# ProPrj_Loongson_Aquarii_v1_7.net
KiCad netlist of a schematic drawn in EasyEDA Pro
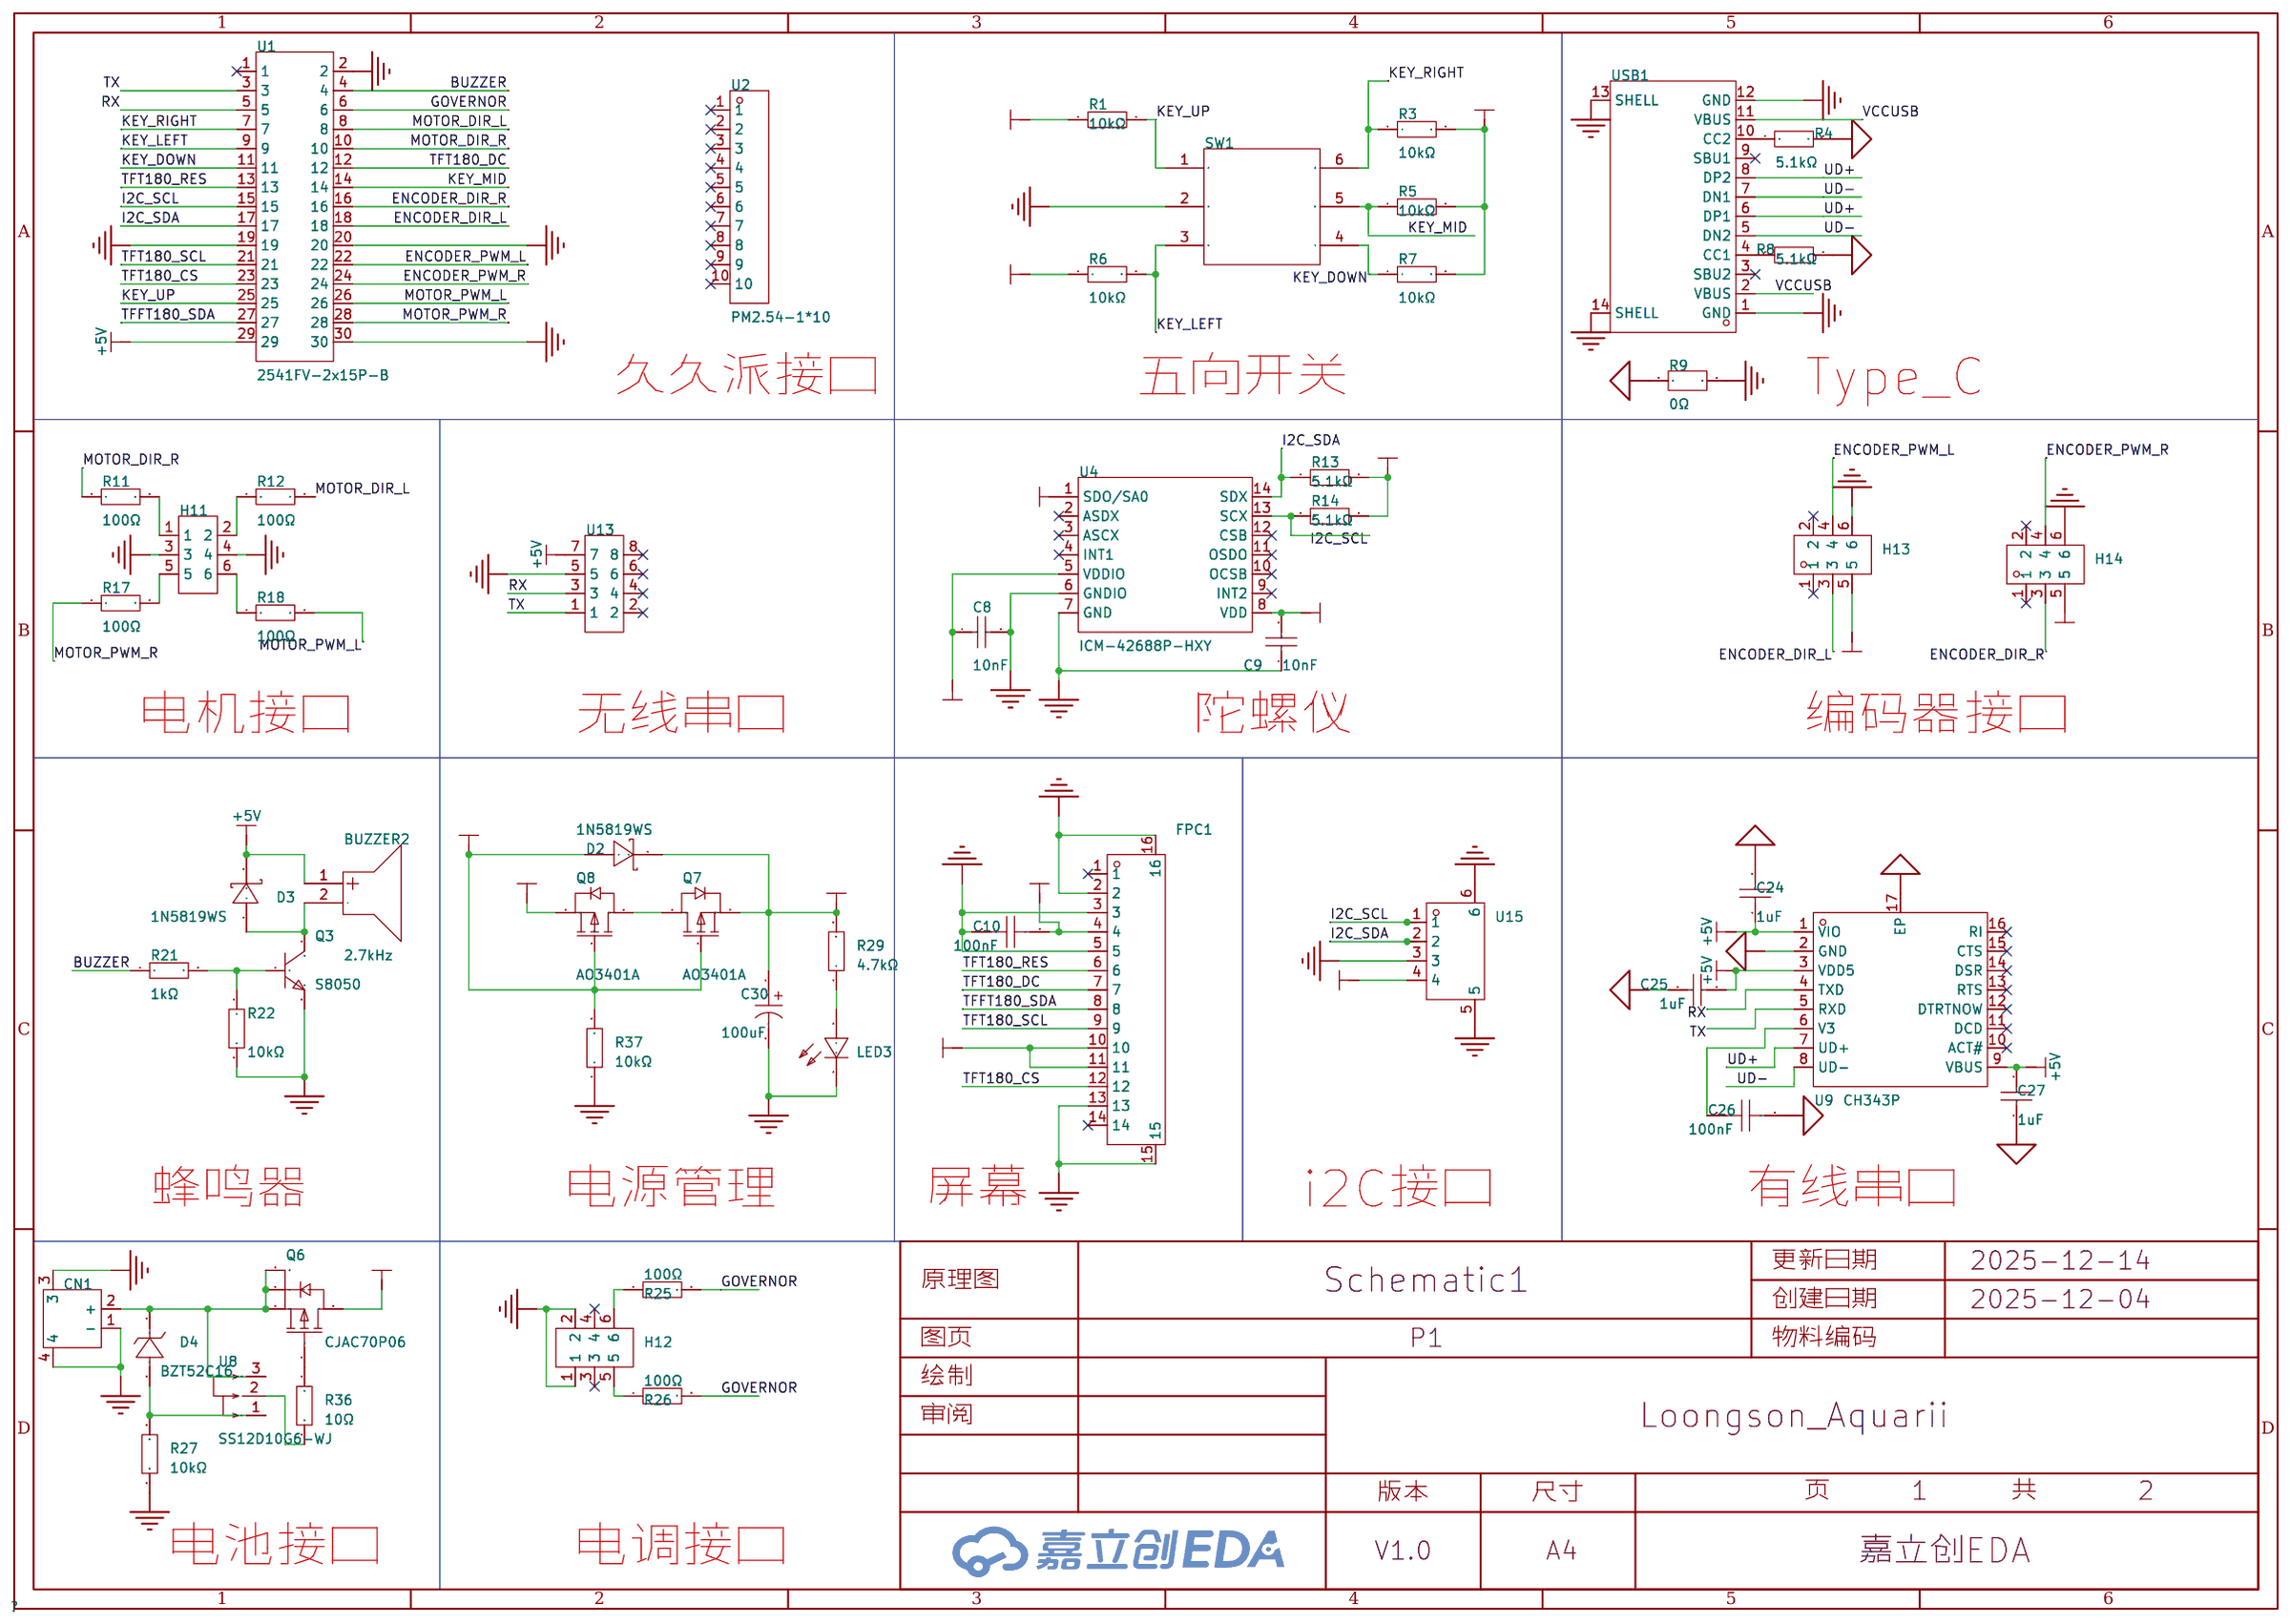
[diagram p0: P1]
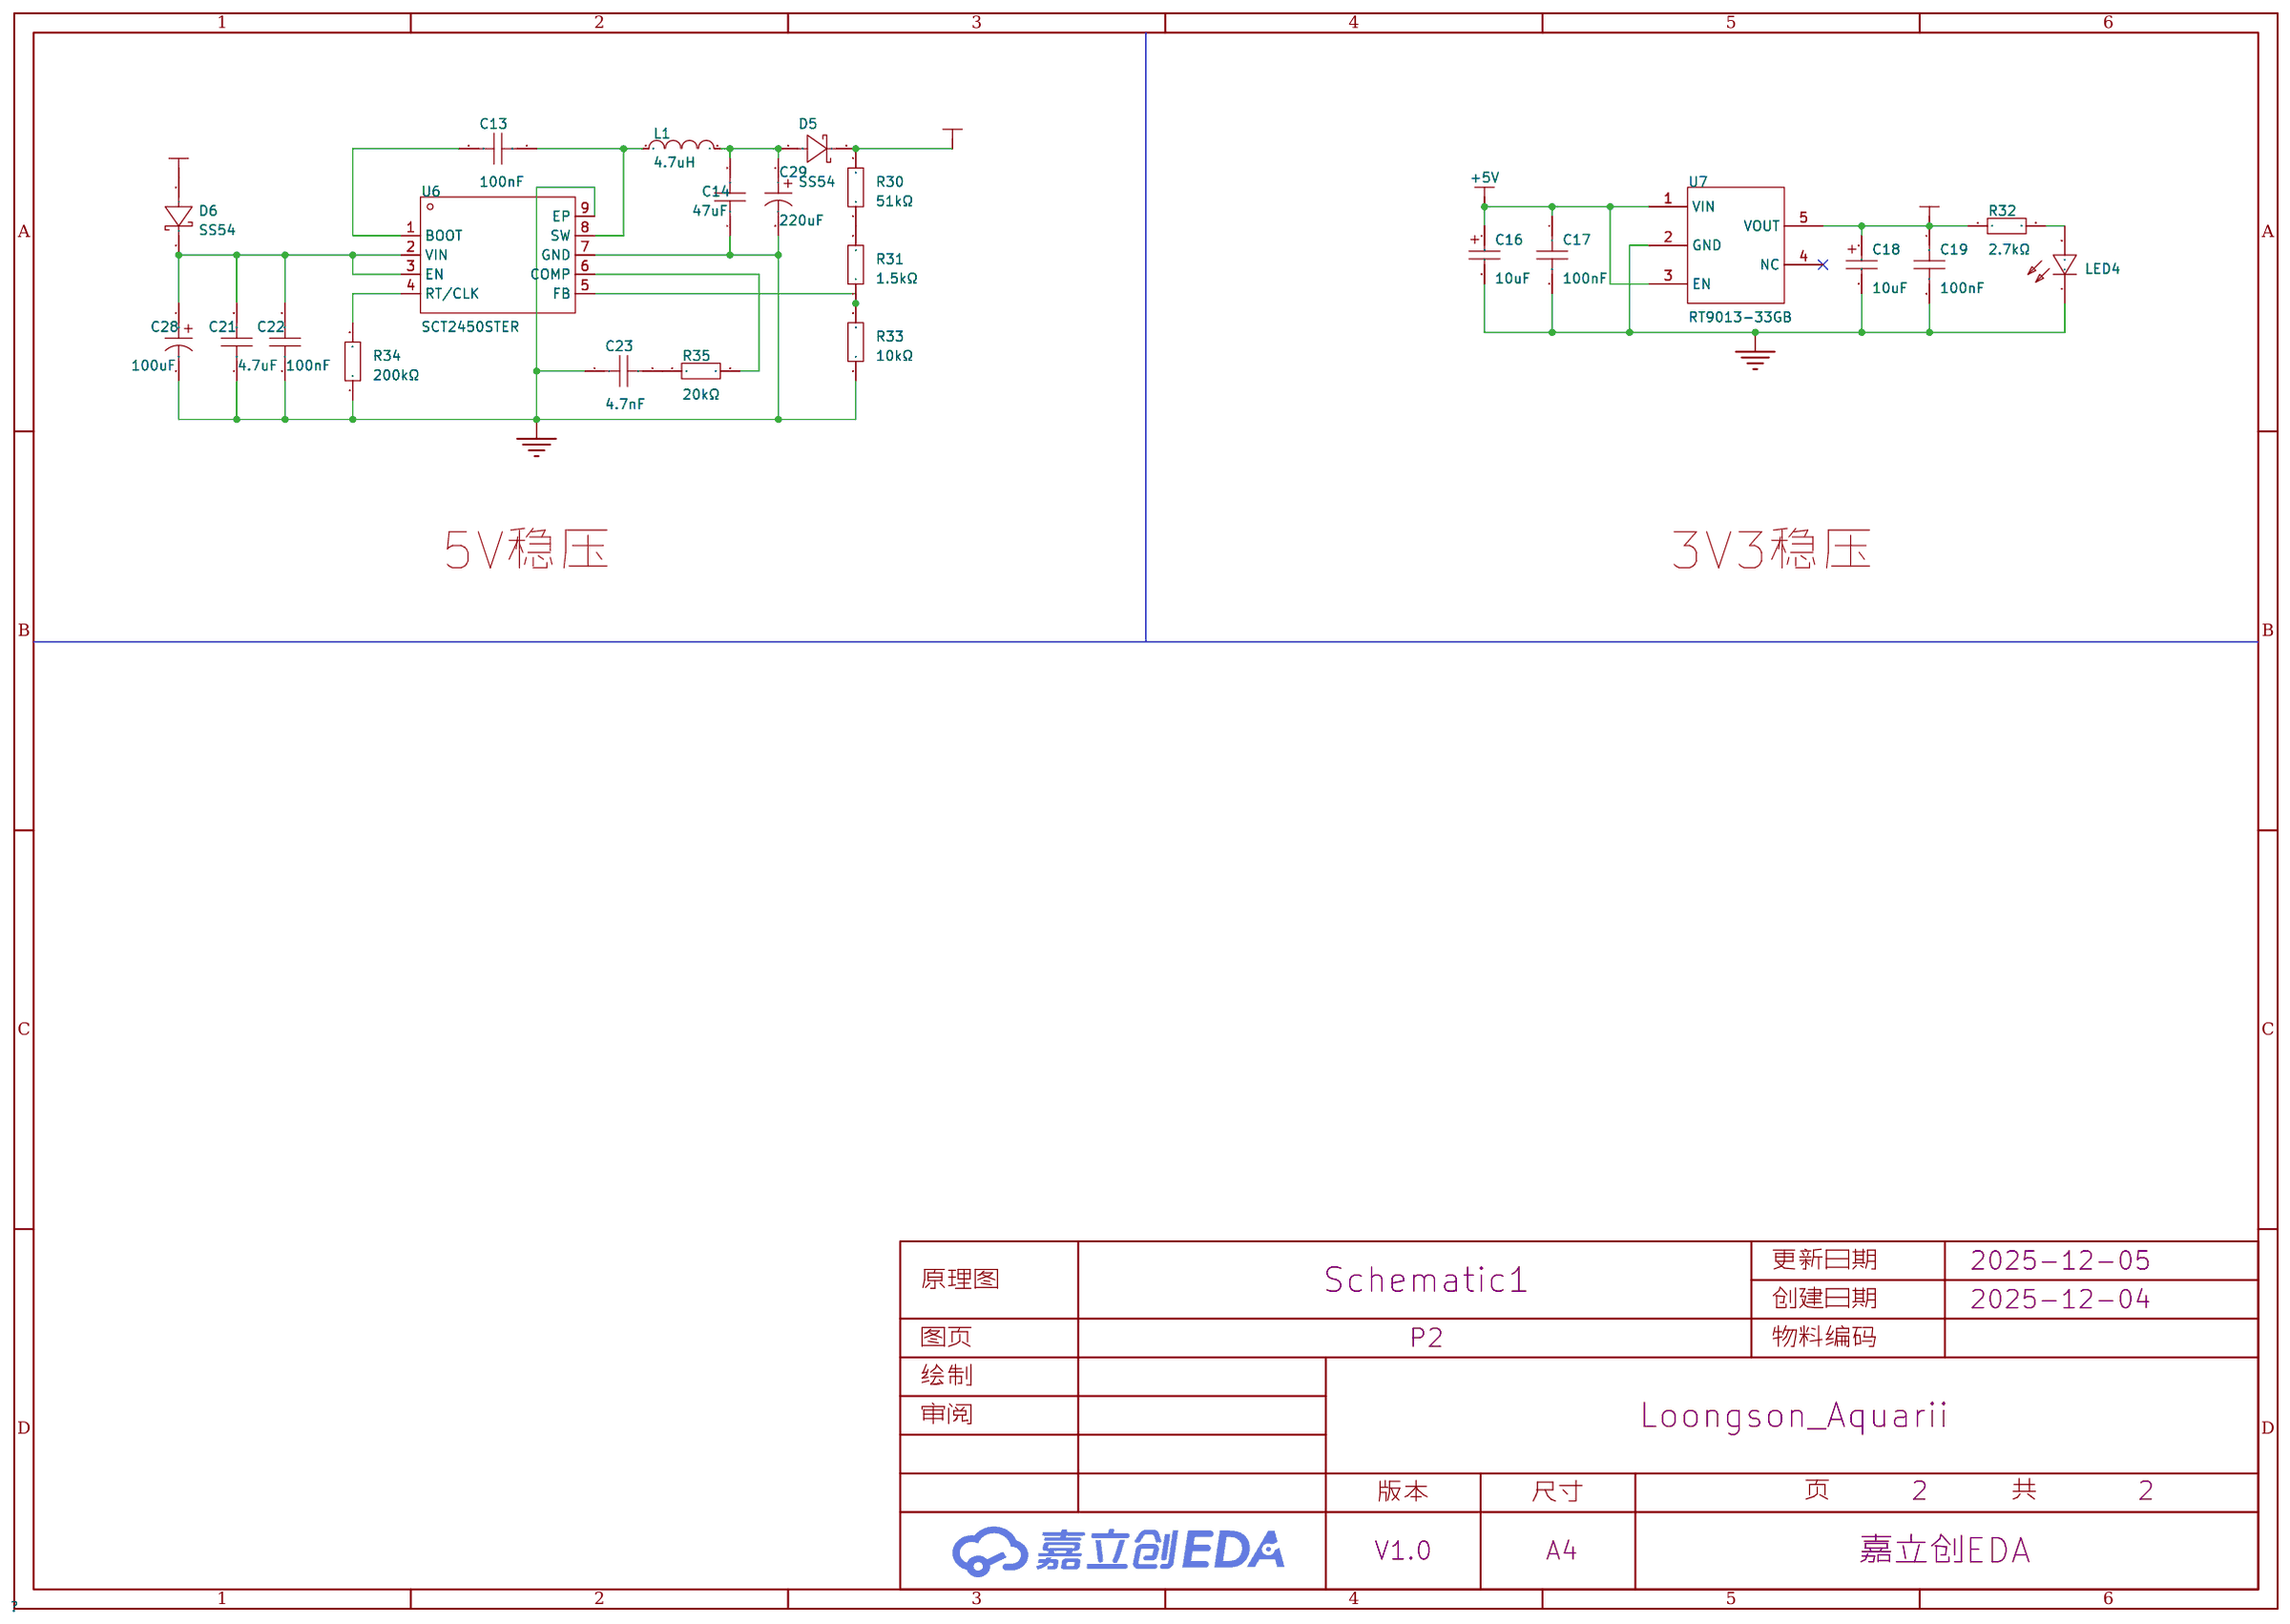
[diagram p1: P2]

(export (version "E")
  (design (tool "Eeschema 10.0.6"))
  (components
    (comp (ref "BUZZER2")
      (value "2.7kHz")
      (footprint "easyedapro:BUZ-SMD_GSC9032RB")
      (description "驱动方式:无源(外部驱动);构造类型:电磁式;额定电压:3.6V;频率:2.7kHz;声压(SPL):85dB;")
      (fields
        (field (name "Manufacturer Part") "GSC9032RB-16R2700")
        (field (name "Manufacturer") "INGHAi(赢海)")
      )
      (libsource (lib "easyedapro") (part "GSC9032RB-16R2700"))
    )
    (comp (ref "C8")
      (value "10nF")
      (footprint "easyedapro:C0603")
      (description "容值:10nF;精度:±10%;额定电压:50V;温度系数:X7R;")
      (fields
        (field (name "Manufacturer Part") "CC0603KRX7R9BB103")
        (field (name "Manufacturer") "YAGEO(国巨)")
      )
      (libsource (lib "easyedapro") (part "CC0603KRX7R9BB103"))
    )
    (comp (ref "C9")
      (value "10nF")
      (footprint "easyedapro:C0603")
      (description "容值:10nF;精度:±10%;额定电压:50V;温度系数:X7R;")
      (fields
        (field (name "Manufacturer Part") "CC0603KRX7R9BB103")
        (field (name "Manufacturer") "YAGEO(国巨)")
      )
      (libsource (lib "easyedapro") (part "CC0603KRX7R9BB103"))
    )
    (comp (ref "C10")
      (value "100nF")
      (footprint "easyedapro:C0603")
      (description "容值:100nF;精度:±10%;额定电压:50V;材质(温度系数):X7R;")
      (fields
        (field (name "Manufacturer Part") "CGA0603X7R104K500JT")
        (field (name "Manufacturer") "HRE(芯声)")
      )
      (libsource (lib "easyedapro") (part "CGA0603X7R104K500JT"))
    )
    (comp (ref "C24")
      (value "1uF")
      (footprint "easyedapro:C0805")
      (description "容值:1uF;精度:±10%;额定电压:50V;温度系数:X7R;")
      (fields
        (field (name "Manufacturer Part") "CL21B105KBFNNNE")
        (field (name "Manufacturer") "SAMSUNG(三星)")
      )
      (libsource (lib "easyedapro") (part "CL21B105KBFNNNE"))
    )
    (comp (ref "C25")
      (value "1uF")
      (footprint "easyedapro:C0805")
      (description "容值:1uF;精度:±10%;额定电压:50V;温度系数:X7R;")
      (fields
        (field (name "Manufacturer Part") "CL21B105KBFNNNE")
        (field (name "Manufacturer") "SAMSUNG(三星)")
      )
      (libsource (lib "easyedapro") (part "CL21B105KBFNNNE"))
    )
    (comp (ref "C26")
      (value "100nF")
      (footprint "easyedapro:C0603")
      (description "容值:100nF;精度:±10%;额定电压:50V;材质(温度系数):X7R;")
      (fields
        (field (name "Manufacturer Part") "CGA0603X7R104K500JT")
        (field (name "Manufacturer") "HRE(芯声)")
      )
      (libsource (lib "easyedapro") (part "CGA0603X7R104K500JT"))
    )
    (comp (ref "C27")
      (value "1uF")
      (footprint "easyedapro:C0805")
      (description "容值:1uF;精度:±10%;额定电压:50V;温度系数:X7R;")
      (fields
        (field (name "Manufacturer Part") "CL21B105KBFNNNE")
        (field (name "Manufacturer") "SAMSUNG(三星)")
      )
      (libsource (lib "easyedapro") (part "CL21B105KBFNNNE"))
    )
    (comp (ref "C30")
      (value "100uF")
      (footprint "easyedapro:CAP-SMD_BD6.3-L6.6-W6.6-FD-1")
      (description "容值:100uF;精度:±20%;额定电压:25V;纹波电流:72mA@120Hz;")
      (fields (field (name "Manufacturer Part") "JVJ25V100M6x5") (field (name "Manufacturer") "JIERR(捷而瑞)"))
      (libsource (lib "easyedapro") (part "JVJ25V100M6X5"))
    )
    (comp (ref "CN1")
      (value "XT30PW-M30.G.Y")
      (footprint "easyedapro:CONN-TH_XT30PW-M")
      (description "类别:-;类型1:-;")
      (fields (field (name "Manufacturer") "AMASS(艾迈斯)"))
      (libsource (lib "easyedapro") (part "XT30PW-M"))
    )
    (comp (ref "D2")
      (value "1N5819WS")
      (footprint "easyedapro:SOD-323_L1.8-W1.3-LS2.5-RD")
      (description "正向压降(Vf):600mV@1A;直流反向耐压(Vr):40V;整流电流:1A;")
      (fields (field (name "Manufacturer") "Hottech(合科泰)"))
      (libsource (lib "easyedapro") (part "1N5819WS"))
    )
    (comp (ref "D3")
      (value "1N5819WS")
      (footprint "easyedapro:SOD-323_L1.8-W1.3-LS2.5-RD")
      (description "正向压降(Vf):600mV@1A;直流反向耐压(Vr):40V;整流电流:1A;")
      (fields (field (name "Manufacturer") "Hottech(合科泰)"))
      (libsource (lib "easyedapro") (part "1N5819WS"))
    )
    (comp (ref "D4")
      (value "BZT52C16")
      (footprint "easyedapro:SOD-123_L2.7-W1.6-LS3.7-RD")
      (description "二极管配置:独立式;稳压值(标称值):16V;稳压值(范围):15.2V~16.8V;耗散功率(Pd):500mW;")
      (fields (field (name "Manufacturer") "宏嘉诚"))
      (libsource (lib "easyedapro") (part "BZT52C16_C19077413"))
    )
    (comp (ref "FPC1")
      (value "HC-FPC-05-09-14RLTAG")
      (footprint "easyedapro:FPC-SMD_14P-P0.50_HC-FPC-05-09-14RLTAG")
      (description "锁定特性:翻盖式;触点类型:双侧触点/上下接;触点数量:14P;间距:0.5mm;安装方式:卧贴;工作温度:-55°C~+85°C;")
      (fields (field (name "Manufacturer") "HCTL(华灿天禄)"))
      (libsource (lib "easyedapro") (part "HC-FPC-05-09-14RLTAG"))
    )
    (comp (ref "H11")
      (value "HX PZ2.54-2x3P TP")
      (footprint "easyedapro:HDR-SMD_6P-P2.54-V-M-R2-C3-LS7.2_M20-8760342")
      (fields (field (name "Manufacturer") "hanxia(韩下)"))
      (libsource (lib "easyedapro") (part "HX PZ2.54-2X3P TP"))
    )
    (comp (ref "H12")
      (value "HX PZ2.54-2x3P TP")
      (footprint "easyedapro:HDR-SMD_6P-P2.54-V-M-R2-C3-LS7.2_M20-8760342")
      (fields (field (name "Manufacturer") "hanxia(韩下)"))
      (libsource (lib "easyedapro") (part "HX PZ2.54-2X3P TP"))
    )
    (comp (ref "H13")
      (value "PZ254V-12-6P")
      (footprint "easyedapro:HDR-TH_6P-P2.54-V-M-R2-C3-S2.54")
      (fields (field (name "Manufacturer") "XFCN(兴飞)"))
      (libsource (lib "easyedapro") (part "PZ254V-12-6P"))
    )
    (comp (ref "H14")
      (value "PZ254V-12-6P")
      (footprint "easyedapro:HDR-TH_6P-P2.54-V-M-R2-C3-S2.54")
      (fields (field (name "Manufacturer") "XFCN(兴飞)"))
      (libsource (lib "easyedapro") (part "PZ254V-12-6P"))
    )
    (comp (ref "LED3")
      (value "NCD0603R1")
      (footprint "easyedapro:LED0603-RD_RED")
      (fields (field (name "Manufacturer") "国星光电"))
      (libsource (lib "easyedapro") (part "FC-DA1608HRK-620D"))
    )
    (comp (ref "Q3")
      (value "S8050")
      (footprint "easyedapro:SOT-23-3_L2.9-W1.6-P1.90-LS2.8-BR")
      (description "晶体管类型:NPN;集电极电流(Ic):500mA;集射极击穿电压(Vceo):25V;功率(Pd):300mW;")
      (fields (field (name "Manufacturer") "Hottech(合科泰)"))
      (libsource (lib "easyedapro") (part "S8050_C181158"))
    )
    (comp (ref "Q6")
      (value "CJAC70P06")
      (footprint "easyedapro:TDSON-8_L5.9-W5.2-P1.27-BL")
      (fields (field (name "Manufacturer") "CJ(江苏长电/长晶)"))
      (libsource (lib "easyedapro") (part "CJAC70P06"))
    )
    (comp (ref "Q7")
      (value "AO3401A")
      (footprint "easyedapro:SOT-23_L2.9-W1.3-P1.90-LS2.4-BR")
      (fields (field (name "Manufacturer") "UMW(友台半导体)"))
      (libsource (lib "easyedapro") (part "AO3401A_C347476"))
    )
    (comp (ref "Q8")
      (value "AO3401A")
      (footprint "easyedapro:SOT-23_L2.9-W1.3-P1.90-LS2.4-BR")
      (fields (field (name "Manufacturer") "UMW(友台半导体)"))
      (libsource (lib "easyedapro") (part "AO3401A_C347476"))
    )
    (comp (ref "R1")
      (value "10kΩ")
      (footprint "easyedapro:R0603")
      (description "电阻类型:厚膜电阻;阻值:10kΩ;精度:±1%;功率:100mW;最大工作电压:75V;温度系数:±100ppm/°C;")
      (fields
        (field (name "Manufacturer Part") "0603WAF1002T5E")
        (field (name "Manufacturer") "UNI-ROYAL(厚声)")
      )
      (libsource (lib "easyedapro") (part "0603WAF1002T5E"))
    )
    (comp (ref "R3")
      (value "10kΩ")
      (footprint "easyedapro:R0603")
      (description "电阻类型:厚膜电阻;阻值:10kΩ;精度:±1%;功率:100mW;最大工作电压:75V;温度系数:±100ppm/°C;")
      (fields
        (field (name "Manufacturer Part") "0603WAF1002T5E")
        (field (name "Manufacturer") "UNI-ROYAL(厚声)")
      )
      (libsource (lib "easyedapro") (part "0603WAF1002T5E"))
    )
    (comp (ref "R4")
      (value "5.1kΩ")
      (footprint "easyedapro:R0603")
      (description "电阻类型:厚膜电阻;阻值:5.1kΩ;精度:±1%;功率:100mW;最大工作电压:75V;温度系数:±100ppm/°C;")
      (fields
        (field (name "Manufacturer Part") "0603WAF5101T5E")
        (field (name "Manufacturer") "UNI-ROYAL(厚声)")
      )
      (libsource (lib "easyedapro") (part "0603WAF5101T5E"))
    )
    (comp (ref "R5")
      (value "10kΩ")
      (footprint "easyedapro:R0603")
      (description "电阻类型:厚膜电阻;阻值:10kΩ;精度:±1%;功率:100mW;最大工作电压:75V;温度系数:±100ppm/°C;")
      (fields
        (field (name "Manufacturer Part") "0603WAF1002T5E")
        (field (name "Manufacturer") "UNI-ROYAL(厚声)")
      )
      (libsource (lib "easyedapro") (part "0603WAF1002T5E"))
    )
    (comp (ref "R6")
      (value "10kΩ")
      (footprint "easyedapro:R0603")
      (description "电阻类型:厚膜电阻;阻值:10kΩ;精度:±1%;功率:100mW;最大工作电压:75V;温度系数:±100ppm/°C;")
      (fields
        (field (name "Manufacturer Part") "0603WAF1002T5E")
        (field (name "Manufacturer") "UNI-ROYAL(厚声)")
      )
      (libsource (lib "easyedapro") (part "0603WAF1002T5E"))
    )
    (comp (ref "R7")
      (value "10kΩ")
      (footprint "easyedapro:R0603")
      (description "电阻类型:厚膜电阻;阻值:10kΩ;精度:±1%;功率:100mW;最大工作电压:75V;温度系数:±100ppm/°C;")
      (fields
        (field (name "Manufacturer Part") "0603WAF1002T5E")
        (field (name "Manufacturer") "UNI-ROYAL(厚声)")
      )
      (libsource (lib "easyedapro") (part "0603WAF1002T5E"))
    )
    (comp (ref "R8")
      (value "5.1kΩ")
      (footprint "easyedapro:R0603")
      (description "电阻类型:厚膜电阻;阻值:5.1kΩ;精度:±1%;功率:100mW;最大工作电压:75V;温度系数:±100ppm/°C;")
      (fields
        (field (name "Manufacturer Part") "0603WAF5101T5E")
        (field (name "Manufacturer") "UNI-ROYAL(厚声)")
      )
      (libsource (lib "easyedapro") (part "0603WAF5101T5E"))
    )
    (comp (ref "R9")
      (value "0Ω")
      (footprint "easyedapro:R1206")
      (description "电阻类型:厚膜电阻;阻值:0Ω;精度:±5%;功率:250mW;最大工作电压:200V;")
      (fields (field (name "Manufacturer Part") "FRC1206P000 TS") (field (name "Manufacturer") "FOJAN(富捷)"))
      (libsource (lib "easyedapro") (part "FRC1206P000 TS"))
    )
    (comp (ref "R11")
      (value "100Ω")
      (footprint "easyedapro:R0603")
      (description "电阻类型:厚膜电阻;阻值:100Ω;精度:±1%;功率:100mW;最大工作电压:75V;温度系数:±200ppm/°C;")
      (fields
        (field (name "Manufacturer Part") "0603WAF1000T5E")
        (field (name "Manufacturer") "UNI-ROYAL(厚声)")
      )
      (libsource (lib "easyedapro") (part "0603WAF1000T5E"))
    )
    (comp (ref "R12")
      (value "100Ω")
      (footprint "easyedapro:R0603")
      (description "电阻类型:厚膜电阻;阻值:100Ω;精度:±1%;功率:100mW;最大工作电压:75V;温度系数:±200ppm/°C;")
      (fields
        (field (name "Manufacturer Part") "0603WAF1000T5E")
        (field (name "Manufacturer") "UNI-ROYAL(厚声)")
      )
      (libsource (lib "easyedapro") (part "0603WAF1000T5E"))
    )
    (comp (ref "R13")
      (value "5.1kΩ")
      (footprint "easyedapro:R0603")
      (description "电阻类型:厚膜电阻;阻值:5.1kΩ;精度:±1%;功率:100mW;最大工作电压:75V;温度系数:±100ppm/°C;")
      (fields
        (field (name "Manufacturer Part") "0603WAF5101T5E")
        (field (name "Manufacturer") "UNI-ROYAL(厚声)")
      )
      (libsource (lib "easyedapro") (part "0603WAF5101T5E"))
    )
    (comp (ref "R14")
      (value "5.1kΩ")
      (footprint "easyedapro:R0603")
      (description "电阻类型:厚膜电阻;阻值:5.1kΩ;精度:±1%;功率:100mW;最大工作电压:75V;温度系数:±100ppm/°C;")
      (fields
        (field (name "Manufacturer Part") "0603WAF5101T5E")
        (field (name "Manufacturer") "UNI-ROYAL(厚声)")
      )
      (libsource (lib "easyedapro") (part "0603WAF5101T5E"))
    )
    (comp (ref "R17")
      (value "100Ω")
      (footprint "easyedapro:R0603")
      (description "电阻类型:厚膜电阻;阻值:100Ω;精度:±1%;功率:100mW;最大工作电压:75V;温度系数:±200ppm/°C;")
      (fields
        (field (name "Manufacturer Part") "0603WAF1000T5E")
        (field (name "Manufacturer") "UNI-ROYAL(厚声)")
      )
      (libsource (lib "easyedapro") (part "0603WAF1000T5E"))
    )
    (comp (ref "R18")
      (value "100Ω")
      (footprint "easyedapro:R0603")
      (description "电阻类型:厚膜电阻;阻值:100Ω;精度:±1%;功率:100mW;最大工作电压:75V;温度系数:±200ppm/°C;")
      (fields
        (field (name "Manufacturer Part") "0603WAF1000T5E")
        (field (name "Manufacturer") "UNI-ROYAL(厚声)")
      )
      (libsource (lib "easyedapro") (part "0603WAF1000T5E"))
    )
    (comp (ref "R21")
      (value "1kΩ")
      (footprint "easyedapro:R0603")
      (description "电阻类型:厚膜电阻;阻值:1kΩ;精度:±1%;功率:100mW;工作电压:75V;温度系数:±100ppm/°C;")
      (fields
        (field (name "Manufacturer Part") "0603WAF1001T5E")
        (field (name "Manufacturer") "UNI-ROYAL(厚声)")
      )
      (libsource (lib "easyedapro") (part "0603WAF1001T5E"))
    )
    (comp (ref "R22")
      (value "10kΩ")
      (footprint "easyedapro:R0603")
      (description "电阻类型:厚膜电阻;阻值:10kΩ;精度:±1%;功率:100mW;最大工作电压:75V;温度系数:±100ppm/°C;")
      (fields
        (field (name "Manufacturer Part") "0603WAF1002T5E")
        (field (name "Manufacturer") "UNI-ROYAL(厚声)")
      )
      (libsource (lib "easyedapro") (part "0603WAF1002T5E"))
    )
    (comp (ref "R25")
      (value "100Ω")
      (footprint "easyedapro:R0603")
      (description "电阻类型:厚膜电阻;阻值:100Ω;精度:±1%;功率:100mW;最大工作电压:75V;温度系数:±200ppm/°C;")
      (fields
        (field (name "Manufacturer Part") "0603WAF1000T5E")
        (field (name "Manufacturer") "UNI-ROYAL(厚声)")
      )
      (libsource (lib "easyedapro") (part "0603WAF1000T5E"))
    )
    (comp (ref "R26")
      (value "100Ω")
      (footprint "easyedapro:R0603")
      (description "电阻类型:厚膜电阻;阻值:100Ω;精度:±1%;功率:100mW;最大工作电压:75V;温度系数:±200ppm/°C;")
      (fields
        (field (name "Manufacturer Part") "0603WAF1000T5E")
        (field (name "Manufacturer") "UNI-ROYAL(厚声)")
      )
      (libsource (lib "easyedapro") (part "0603WAF1000T5E"))
    )
    (comp (ref "R27")
      (value "10kΩ")
      (footprint "easyedapro:R0603")
      (description "电阻类型:厚膜电阻;阻值:10kΩ;精度:±1%;功率:100mW;最大工作电压:75V;温度系数:±100ppm/°C;")
      (fields
        (field (name "Manufacturer Part") "0603WAF1002T5E")
        (field (name "Manufacturer") "UNI-ROYAL(厚声)")
      )
      (libsource (lib "easyedapro") (part "0603WAF1002T5E"))
    )
    (comp (ref "R29")
      (value "4.7kΩ")
      (footprint "easyedapro:R0603")
      (description "电阻类型:厚膜电阻;阻值:4.7kΩ;精度:±1%;功率:100mW;最大工作电压:75V;温度系数:±100ppm/°C;")
      (fields
        (field (name "Manufacturer Part") "0603WAF4701T5E")
        (field (name "Manufacturer") "UNI-ROYAL(厚声)")
      )
      (libsource (lib "easyedapro") (part "0603WAF4701T5E"))
    )
    (comp (ref "R36")
      (value "10Ω")
      (footprint "easyedapro:R0603")
      (description "电阻类型:厚膜电阻;阻值:10Ω;精度:±1%;功率:100mW;最大工作电压:75V;温度系数:±400ppm/°C;")
      (fields
        (field (name "Manufacturer Part") "0603WAF100JT5E")
        (field (name "Manufacturer") "UNI-ROYAL(厚声)")
      )
      (libsource (lib "easyedapro") (part "0603WAF100JT5E"))
    )
    (comp (ref "R37")
      (value "10kΩ")
      (footprint "easyedapro:R0603")
      (description "电阻类型:厚膜电阻;阻值:10kΩ;精度:±1%;功率:100mW;最大工作电压:75V;温度系数:±100ppm/°C;")
      (fields
        (field (name "Manufacturer Part") "0603WAF1002T5E")
        (field (name "Manufacturer") "UNI-ROYAL(厚声)")
      )
      (libsource (lib "easyedapro") (part "0603WAF1002T5E"))
    )
    (comp (ref "SW1")
      (value "7*7*5-6P-L WX")
      (footprint "easyedapro:SW-SMD_8P-L7.0-W7.0-P1.40-LS7.4-TL")
      (fields (field (name "Manufacturer") "SHOU HAN(首韩)"))
      (libsource (lib "easyedapro") (part "7*7*5-6P-L WX"))
    )
    (comp (ref "U1")
      (value "2541FV-2x15P-B")
      (footprint "easyedapro:HDR-TH_30P-P2.54-V-F-R2-C15-S2.54")
      (fields (field (name "Manufacturer") "HanElectricity(瀚源)"))
      (libsource (lib "easyedapro") (part "2541FV-2X15P-B"))
    )
    (comp (ref "U2")
      (value "PM2.54-1*10")
      (footprint "easyedapro:HDR-TH_10P-P2.54-V-F")
      (fields (field (name "Manufacturer") "ZHOURI(洲日)"))
      (libsource (lib "easyedapro") (part "PM2.54-1*10"))
    )
    (comp (ref "U4")
      (value "ICM-42688P-HXY")
      (footprint "easyedapro:LGA-14_L3.0-W2.5-P0.50-TL")
      (fields (field (name "Manufacturer") "HXY MOSFET(华轩阳电子)"))
      (libsource (lib "easyedapro") (part "ICM-42688P-HXY"))
    )
    (comp (ref "U8")
      (value "SS12D10G6-WJ")
      (footprint "easyedapro:SW-TH_3P-P4.80_HX-SS12D10G6-WJ")
      (description "电路结构:单刀双掷;安装方式:弯插;开关颜色:黑色;额定电流:2A;额定电压:125V;工作寿命:3千次;")
      (fields (field (name "Manufacturer") "SHOU HAN(首韩)"))
      (libsource (lib "easyedapro") (part "SS12D10G6-WJ"))
    )
    (comp (ref "U9")
      (value "CH343P")
      (footprint "easyedapro:TQFN-16_L3.0-W3.0-P0.50-BL-EP1.7")
      (description "应用功能:USB转UART;USB协议版本:USB 2.0;通道数:-;数据速率:6Mbps;")
      (fields (field (name "Manufacturer") "WCH(南京沁恒)"))
      (libsource (lib "easyedapro") (part "CH343P"))
    )
    (comp (ref "U13")
      (value "5BME8-08872-204-W0")
      (footprint "easyedapro:CONN-SMD_5BME8-08872-204-W0")
      (fields (field (name "Manufacturer") "SAMZO(三佐)"))
      (libsource (lib "easyedapro") (part "5BME8-08872-204-W0"))
    )
    (comp (ref "U15")
      (value "2.54-4PWTDK")
      (footprint "easyedapro:CONN-SMD_4P-P2.50_SHOU_2.54-4PWTDK")
      (fields (field (name "Manufacturer") "SHOU HAN(首韩)"))
      (libsource (lib "easyedapro") (part "2.54-4PWTDK"))
    )
    (comp (ref "USB1")
      (value "TYPE-C 16PIN 2MD(073)")
      (footprint "easyedapro:USB-C-SMD_TYPE-C-6PIN-2MD-073")
      (description "连接器类型:Type-C;标准:USB 3.1;公母:母;安装方式:卧贴;触点数量:16P;端口数量:1;额定电流 - 电源:5A;工作温度范围:-25°C~+85°C;")
      (fields (field (name "Manufacturer") "SHOU HAN(首韩)"))
      (libsource (lib "easyedapro") (part "TYPE-C 16PIN 2MD(073)"))
    )
    (comp (ref "C13")
      (value "100nF")
      (footprint "easyedapro:C0603")
      (description "容值:100nF;精度:±10%;额定电压:50V;材质(温度系数):X7R;")
      (fields
        (field (name "Manufacturer Part") "CGA0603X7R104K500JT")
        (field (name "Manufacturer") "HRE(芯声)")
      )
      (libsource (lib "easyedapro") (part "CGA0603X7R104K500JT"))
    )
    (comp (ref "C14")
      (value "47uF")
      (footprint "easyedapro:C1206")
      (description "容值:47uF;精度:±20%;额定电压:25V;材质(温度系数):X5R;")
      (fields
        (field (name "Manufacturer Part") "CGA1206X5R476M250NT")
        (field (name "Manufacturer") "HRE(芯声)")
      )
      (libsource (lib "easyedapro") (part "CGA1206X5R476M250NT"))
    )
    (comp (ref "C16")
      (value "10uF")
      (footprint "easyedapro:CAP-SMD_L3.2-W1.6-RD-C7171")
      (description "容值:10uF;精度:±10%;额定电压:16V;等效串联电阻:3Ω@100kHz;")
      (fields (field (name "Manufacturer Part") "TAJA106K016RNJ") (field (name "Manufacturer") "Kyocera AVX"))
      (libsource (lib "easyedapro") (part "TAJA106K016RNJ"))
    )
    (comp (ref "C17")
      (value "100nF")
      (footprint "easyedapro:C0603")
      (description "容值:100nF;精度:±10%;额定电压:50V;材质(温度系数):X7R;")
      (fields
        (field (name "Manufacturer Part") "CGA0603X7R104K500JT")
        (field (name "Manufacturer") "HRE(芯声)")
      )
      (libsource (lib "easyedapro") (part "CGA0603X7R104K500JT"))
    )
    (comp (ref "C18")
      (value "10uF")
      (footprint "easyedapro:CAP-SMD_L3.2-W1.6-RD-C7171")
      (description "容值:10uF;精度:±10%;额定电压:16V;等效串联电阻:3Ω@100kHz;")
      (fields (field (name "Manufacturer Part") "TAJA106K016RNJ") (field (name "Manufacturer") "Kyocera AVX"))
      (libsource (lib "easyedapro") (part "TAJA106K016RNJ"))
    )
    (comp (ref "C19")
      (value "100nF")
      (footprint "easyedapro:C0603")
      (description "容值:100nF;精度:±10%;额定电压:50V;材质(温度系数):X7R;")
      (fields
        (field (name "Manufacturer Part") "CGA0603X7R104K500JT")
        (field (name "Manufacturer") "HRE(芯声)")
      )
      (libsource (lib "easyedapro") (part "CGA0603X7R104K500JT"))
    )
    (comp (ref "C21")
      (value "4.7uF")
      (footprint "easyedapro:C1206")
      (description "容值:4.7uF;精度:±10%;额定电压:35V;材质(温度系数):X5R;")
      (fields
        (field (name "Manufacturer Part") "CGA1206X5R475K350NT")
        (field (name "Manufacturer") "HRE(芯声)")
      )
      (libsource (lib "easyedapro") (part "CGA1206X5R475K350NT"))
    )
    (comp (ref "C22")
      (value "100nF")
      (footprint "easyedapro:C0603")
      (description "容值:100nF;精度:±10%;额定电压:50V;材质(温度系数):X7R;")
      (fields
        (field (name "Manufacturer Part") "CGA0603X7R104K500JT")
        (field (name "Manufacturer") "HRE(芯声)")
      )
      (libsource (lib "easyedapro") (part "CGA0603X7R104K500JT"))
    )
    (comp (ref "C23")
      (value "4.7nF")
      (footprint "easyedapro:C0603")
      (description "容值:4.7nF;精度:±10%;额定电压:50V;材质(温度系数):X7R;")
      (fields
        (field (name "Manufacturer Part") "CGA0603X7R472K500JT")
        (field (name "Manufacturer") "HRE(芯声)")
      )
      (libsource (lib "easyedapro") (part "CGA0603X7R472K500JT"))
    )
    (comp (ref "C28")
      (value "100uF")
      (footprint "easyedapro:CAP-SMD_BD6.3-L6.6-W6.6-FD-1")
      (description "容值:100uF;精度:±20%;额定电压:25V;纹波电流:72mA@120Hz;")
      (fields (field (name "Manufacturer Part") "JVJ25V100M6x5") (field (name "Manufacturer") "JIERR(捷而瑞)"))
      (libsource (lib "easyedapro") (part "JVJ25V100M6X5"))
    )
    (comp (ref "C29")
      (value "220uF")
      (footprint "easyedapro:CAP-SMD_BD6.3-L6.6-W6.6-LS7.3-FD-H7.7")
      (description "容值:220uF;精度:±20%;额定电压:25V;纹波电流:120mA@120Hz;")
      (fields (field (name "Manufacturer Part") "JVJ25V220M6x8") (field (name "Manufacturer") "JIERR(捷而瑞)"))
      (libsource (lib "easyedapro") (part "JVJ25V220M6X8"))
    )
    (comp (ref "D5")
      (value "SS54")
      (footprint "easyedapro:SMA_L4.3-W2.6-LS5.0-FD")
      (description "二极管配置:独立式;正向压降(Vf):550mV@5.0A;直流反向耐压(Vr):40V;整流电流:5A;")
      (fields (field (name "Manufacturer") "宏迦橙"))
      (libsource (lib "easyedapro") (part "SS54_C7420369"))
    )
    (comp (ref "D6")
      (value "SS54")
      (footprint "easyedapro:SMA_L4.3-W2.6-LS5.0-FD")
      (description "二极管配置:独立式;正向压降(Vf):550mV@5.0A;直流反向耐压(Vr):40V;整流电流:5A;")
      (fields (field (name "Manufacturer") "宏迦橙"))
      (libsource (lib "easyedapro") (part "SS54_C7420369"))
    )
    (comp (ref "L1")
      (value "4.7uH")
      (footprint "easyedapro:IND-SMD_L5.4-W5.2_FXL0530")
      (description "电感值:4.7uH;精度:±20%;额定电流:4.5A;饱和电流(Isat):5A;类型:一体成型电感;")
      (fields (field (name "Manufacturer Part") "FXL0530-4R7-M") (field (name "Manufacturer") "cjiang(长江微电)"))
      (libsource (lib "easyedapro") (part "FXL0530-4R7-M"))
    )
    (comp (ref "LED4")
      (value "NCD0603R1")
      (footprint "easyedapro:LED0603-RD_RED")
      (fields (field (name "Manufacturer") "国星光电"))
      (libsource (lib "easyedapro") (part "FC-DA1608HRK-620D"))
    )
    (comp (ref "R30")
      (value "51kΩ")
      (footprint "easyedapro:R0603")
      (description "电阻类型:厚膜电阻;阻值:51kΩ;精度:±1%;功率:100mW;最大工作电压:75V;温度系数:±100ppm/°C;")
      (fields
        (field (name "Manufacturer Part") "0603WAF5102T5E")
        (field (name "Manufacturer") "UNI-ROYAL(厚声)")
      )
      (libsource (lib "easyedapro") (part "0603WAF5102T5E"))
    )
    (comp (ref "R31")
      (value "1.5kΩ")
      (footprint "easyedapro:R0603")
      (description "电阻类型:厚膜电阻;阻值:1.5kΩ;精度:±1%;功率:100mW;最大工作电压:75V;温度系数:±100ppm/°C;")
      (fields
        (field (name "Manufacturer Part") "0603WAF1501T5E")
        (field (name "Manufacturer") "UNI-ROYAL(厚声)")
      )
      (libsource (lib "easyedapro") (part "0603WAF1501T5E"))
    )
    (comp (ref "R32")
      (value "2.7kΩ")
      (footprint "easyedapro:R0603")
      (description "电阻类型:厚膜电阻;阻值:2.7kΩ;精度:±1%;功率:100mW;最大工作电压:75V;温度系数:±100ppm/°C;")
      (fields
        (field (name "Manufacturer Part") "0603WAF2701T5E")
        (field (name "Manufacturer") "UNI-ROYAL(厚声)")
      )
      (libsource (lib "easyedapro") (part "0603WAF2701T5E"))
    )
    (comp (ref "R33")
      (value "10kΩ")
      (footprint "easyedapro:R0603")
      (description "电阻类型:厚膜电阻;阻值:10kΩ;精度:±1%;功率:100mW;最大工作电压:75V;温度系数:±100ppm/°C;")
      (fields
        (field (name "Manufacturer Part") "0603WAF1002T5E")
        (field (name "Manufacturer") "UNI-ROYAL(厚声)")
      )
      (libsource (lib "easyedapro") (part "0603WAF1002T5E"))
    )
    (comp (ref "R34")
      (value "200kΩ")
      (footprint "easyedapro:R0603")
      (description "电阻类型:厚膜电阻;阻值:200kΩ;精度:±1%;功率:100mW;最大工作电压:75V;温度系数:±100ppm/°C;")
      (fields
        (field (name "Manufacturer Part") "0603WAF2003T5E")
        (field (name "Manufacturer") "UNI-ROYAL(厚声)")
      )
      (libsource (lib "easyedapro") (part "0603WAF2003T5E"))
    )
    (comp (ref "R35")
      (value "20kΩ")
      (footprint "easyedapro:R0603")
      (description "电阻类型:厚膜电阻;阻值:20kΩ;精度:±1%;功率:100mW;最大工作电压:75V;温度系数:±100ppm/°C;")
      (fields
        (field (name "Manufacturer Part") "0603WAF2002T5E")
        (field (name "Manufacturer") "UNI-ROYAL(厚声)")
      )
      (libsource (lib "easyedapro") (part "0603WAF2002T5E"))
    )
    (comp (ref "U6")
      (value "SCT2450STER")
      (footprint "easyedapro:ESOP-8_L4.9-W3.9-P1.27-LS6.0-BL-EP")
      (description "功能类型:降压型;工作电压:3.8V~36V;输出电流:5A;")
      (fields (field (name "Manufacturer") "SCT(芯洲科技)"))
      (libsource (lib "easyedapro") (part "SCT2450STER"))
    )
    (comp (ref "U7")
      (value "RT9013-33GB")
      (footprint "easyedapro:SOT-23-5_L3.0-W1.7-P0.95-LS2.8-BL")
      (description "输出类型:固定;最大输入电压:5.5V;输出电压:3.3V;输出电流:500mA;电源纹波抑制比(PSRR):50dB@(10kHz);输出极性:正极;")
      (fields (field (name "Manufacturer") "RICHTEK(立锜)"))
      (libsource (lib "easyedapro") (part "RT9013-33GB"))
    )
  )
  (nets
    (net (code "1") (name "+5V") (class "Default")
      (node (ref "BUZZER2") (pin "1") (pinfunction "+_1") (pintype "unspecified"))
      (node (ref "C16") (pin "1") (pinfunction "1_1") (pintype "input"))
      (node (ref "C17") (pin "1") (pinfunction "1_1") (pintype "unspecified"))
      (node (ref "C24") (pin "1") (pinfunction "1_1") (pintype "input"))
      (node (ref "C25") (pin "1") (pinfunction "1_1") (pintype "input"))
      (node (ref "C27") (pin "2") (pinfunction "2_2") (pintype "input"))
      (node (ref "C30") (pin "1") (pinfunction "1_1") (pintype "input"))
      (node (ref "D2") (pin "1") (pinfunction "K_1") (pintype "unspecified"))
      (node (ref "D3") (pin "1") (pinfunction "K_1") (pintype "unspecified"))
      (node (ref "Q7") (pin "2") (pinfunction "S_2") (pintype "unspecified"))
      (node (ref "R29") (pin "2") (pinfunction "2_2") (pintype "input"))
      (node (ref "U1") (pin "29") (pinfunction "29_29") (pintype "unspecified"))
      (node (ref "U13") (pin "7") (pinfunction "7_7") (pintype "unspecified"))
      (node (ref "U7") (pin "1") (pinfunction "VIN_1") (pintype "unspecified"))
      (node (ref "U7") (pin "3") (pinfunction "EN_3") (pintype "unspecified"))
      (node (ref "U9") (pin "1") (pinfunction "VIO_1") (pintype "unspecified"))
      (node (ref "U9") (pin "3") (pinfunction "VDD5_3") (pintype "unspecified"))
      (node (ref "U9") (pin "9") (pinfunction "VBUS_9") (pintype "unspecified"))
    )
    (net (code "2") (name "3V3") (class "Default")
      (node (ref "C10") (pin "2") (pinfunction "2_2") (pintype "unspecified"))
      (node (ref "C18") (pin "1") (pinfunction "1_1") (pintype "input"))
      (node (ref "C19") (pin "1") (pinfunction "1_1") (pintype "unspecified"))
      (node (ref "C8") (pin "1") (pinfunction "1_1") (pintype "input"))
      (node (ref "C9") (pin "2") (pinfunction "2_2") (pintype "input"))
      (node (ref "FPC1") (pin "10") (pinfunction "10_10") (pintype "unspecified"))
      (node (ref "FPC1") (pin "11") (pinfunction "11_11") (pintype "unspecified"))
      (node (ref "FPC1") (pin "4") (pinfunction "4_4") (pintype "unspecified"))
      (node (ref "H13") (pin "5") (pinfunction "5_5") (pintype "unspecified"))
      (node (ref "H14") (pin "5") (pinfunction "5_5") (pintype "unspecified"))
      (node (ref "R1") (pin "1") (pinfunction "1_1") (pintype "input"))
      (node (ref "R13") (pin "2") (pinfunction "2_2") (pintype "input"))
      (node (ref "R14") (pin "2") (pinfunction "2_2") (pintype "input"))
      (node (ref "R3") (pin "2") (pinfunction "2_2") (pintype "input"))
      (node (ref "R32") (pin "1") (pinfunction "1_1") (pintype "input"))
      (node (ref "R5") (pin "2") (pinfunction "2_2") (pintype "input"))
      (node (ref "R6") (pin "1") (pinfunction "1_1") (pintype "input"))
      (node (ref "R7") (pin "2") (pinfunction "2_2") (pintype "input"))
      (node (ref "U15") (pin "4") (pinfunction "4_4") (pintype "unspecified"))
      (node (ref "U4") (pin "1") (pinfunction "SDO/SA0_1") (pintype "unspecified"))
      (node (ref "U4") (pin "5") (pinfunction "VDDIO_5") (pintype "unspecified"))
      (node (ref "U4") (pin "8") (pinfunction "VDD_8") (pintype "unspecified"))
      (node (ref "U7") (pin "5") (pinfunction "VOUT_5") (pintype "unspecified"))
    )
    (net (code "3") (name "AGND") (class "Default")
      (node (ref "C24") (pin "2") (pinfunction "2_2") (pintype "input"))
      (node (ref "C25") (pin "2") (pinfunction "2_2") (pintype "input"))
      (node (ref "C26") (pin "2") (pinfunction "2_2") (pintype "unspecified"))
      (node (ref "C27") (pin "1") (pinfunction "1_1") (pintype "input"))
      (node (ref "R4") (pin "2") (pinfunction "2_2") (pintype "input"))
      (node (ref "R8") (pin "2") (pinfunction "2_2") (pintype "input"))
      (node (ref "R9") (pin "1") (pinfunction "1_1") (pintype "unspecified"))
      (node (ref "U9") (pin "17") (pinfunction "EP_17") (pintype "unspecified"))
      (node (ref "U9") (pin "2") (pinfunction "GND_2") (pintype "unspecified"))
    )
    (net (code "4") (name "BUZZER") (class "Default")
      (node (ref "R21") (pin "1") (pinfunction "1_1") (pintype "input"))
      (node (ref "U1") (pin "4") (pinfunction "4_4") (pintype "unspecified"))
    )
    (net (code "5") (name "ENCODER_DIR_L") (class "Default")
      (node (ref "H13") (pin "3") (pinfunction "3_3") (pintype "unspecified"))
      (node (ref "U1") (pin "18") (pinfunction "18_18") (pintype "unspecified"))
    )
    (net (code "6") (name "ENCODER_DIR_R") (class "Default")
      (node (ref "H14") (pin "3") (pinfunction "3_3") (pintype "unspecified"))
      (node (ref "U1") (pin "16") (pinfunction "16_16") (pintype "unspecified"))
    )
    (net (code "7") (name "ENCODER_PWM_L") (class "Default")
      (node (ref "H13") (pin "4") (pinfunction "4_4") (pintype "unspecified"))
      (node (ref "U1") (pin "22") (pinfunction "22_22") (pintype "unspecified"))
    )
    (net (code "8") (name "ENCODER_PWM_R") (class "Default")
      (node (ref "H14") (pin "4") (pinfunction "4_4") (pintype "unspecified"))
      (node (ref "U1") (pin "24") (pinfunction "24_24") (pintype "unspecified"))
    )
    (net (code "9") (name "GND") (class "Default")
      (node (ref "C10") (pin "1") (pinfunction "1_1") (pintype "unspecified"))
      (node (ref "C14") (pin "1") (pinfunction "1_1") (pintype "unspecified"))
      (node (ref "C16") (pin "2") (pinfunction "2_2") (pintype "input"))
      (node (ref "C17") (pin "2") (pinfunction "2_2") (pintype "unspecified"))
      (node (ref "C18") (pin "2") (pinfunction "2_2") (pintype "input"))
      (node (ref "C19") (pin "2") (pinfunction "2_2") (pintype "unspecified"))
      (node (ref "C21") (pin "1") (pinfunction "1_1") (pintype "unspecified"))
      (node (ref "C22") (pin "1") (pinfunction "1_1") (pintype "unspecified"))
      (node (ref "C23") (pin "1") (pinfunction "1_1") (pintype "unspecified"))
      (node (ref "C28") (pin "2") (pinfunction "2_2") (pintype "input"))
      (node (ref "C29") (pin "2") (pinfunction "2_2") (pintype "input"))
      (node (ref "C30") (pin "2") (pinfunction "2_2") (pintype "input"))
      (node (ref "C8") (pin "2") (pinfunction "2_2") (pintype "input"))
      (node (ref "C9") (pin "1") (pinfunction "1_1") (pintype "input"))
      (node (ref "CN1") (pin "1") (pinfunction "-_1") (pintype "unspecified"))
      (node (ref "CN1") (pin "3") (pinfunction "3_3") (pintype "unspecified"))
      (node (ref "CN1") (pin "4") (pinfunction "4_4") (pintype "unspecified"))
      (node (ref "FPC1") (pin "13") (pinfunction "13_13") (pintype "unspecified"))
      (node (ref "FPC1") (pin "15") (pinfunction "15_15") (pintype "unspecified"))
      (node (ref "FPC1") (pin "16") (pinfunction "16_16") (pintype "unspecified"))
      (node (ref "FPC1") (pin "2") (pinfunction "2_2") (pintype "unspecified"))
      (node (ref "FPC1") (pin "3") (pinfunction "3_3") (pintype "unspecified"))
      (node (ref "FPC1") (pin "5") (pinfunction "5_5") (pintype "unspecified"))
      (node (ref "H11") (pin "3") (pinfunction "3_3") (pintype "unspecified"))
      (node (ref "H11") (pin "4") (pinfunction "4_4") (pintype "unspecified"))
      (node (ref "H12") (pin "1") (pinfunction "1_1") (pintype "unspecified"))
      (node (ref "H12") (pin "2") (pinfunction "2_2") (pintype "unspecified"))
      (node (ref "H13") (pin "6") (pinfunction "6_6") (pintype "unspecified"))
      (node (ref "H14") (pin "6") (pinfunction "6_6") (pintype "unspecified"))
      (node (ref "LED3") (pin "1") (pinfunction "K_1") (pintype "input"))
      (node (ref "LED4") (pin "1") (pinfunction "K_1") (pintype "input"))
      (node (ref "Q3") (pin "2") (pinfunction "2_2") (pintype "input"))
      (node (ref "R22") (pin "2") (pinfunction "2_2") (pintype "input"))
      (node (ref "R27") (pin "1") (pinfunction "1_1") (pintype "input"))
      (node (ref "R33") (pin "1") (pinfunction "1_1") (pintype "input"))
      (node (ref "R34") (pin "1") (pinfunction "1_1") (pintype "input"))
      (node (ref "R37") (pin "1") (pinfunction "1_1") (pintype "input"))
      (node (ref "R9") (pin "2") (pinfunction "2_2") (pintype "unspecified"))
      (node (ref "SW1") (pin "2") (pinfunction "2_2") (pintype "unspecified"))
      (node (ref "U1") (pin "19") (pinfunction "19_19") (pintype "unspecified"))
      (node (ref "U1") (pin "2") (pinfunction "2_2") (pintype "unspecified"))
      (node (ref "U1") (pin "20") (pinfunction "20_20") (pintype "unspecified"))
      (node (ref "U1") (pin "30") (pinfunction "30_30") (pintype "unspecified"))
      (node (ref "U13") (pin "5") (pinfunction "5_5") (pintype "unspecified"))
      (node (ref "U15") (pin "3") (pinfunction "3_3") (pintype "unspecified"))
      (node (ref "U15") (pin "5") (pinfunction "5_5") (pintype "unspecified"))
      (node (ref "U15") (pin "6") (pinfunction "6_6") (pintype "unspecified"))
      (node (ref "U4") (pin "6") (pinfunction "GNDIO_6") (pintype "unspecified"))
      (node (ref "U4") (pin "7") (pinfunction "GND_7") (pintype "unspecified"))
      (node (ref "U6") (pin "7") (pinfunction "GND_7") (pintype "unspecified"))
      (node (ref "U6") (pin "9") (pinfunction "EP_9") (pintype "unspecified"))
      (node (ref "U7") (pin "2") (pinfunction "GND_2") (pintype "unspecified"))
      (node (ref "USB1") (pin "1") (pinfunction "GND_1") (pintype "unspecified"))
      (node (ref "USB1") (pin "12") (pinfunction "GND_12") (pintype "unspecified"))
      (node (ref "USB1") (pin "13") (pinfunction "SHELL_13") (pintype "unspecified"))
      (node (ref "USB1") (pin "14") (pinfunction "SHELL_14") (pintype "unspecified"))
    )
    (net (code "10") (name "GOVERNOR") (class "Default")
      (node (ref "R25") (pin "2") (pinfunction "2_2") (pintype "input"))
      (node (ref "R26") (pin "2") (pinfunction "2_2") (pintype "input"))
      (node (ref "U1") (pin "6") (pinfunction "6_6") (pintype "unspecified"))
    )
    (net (code "11") (name "I2C_SCL") (class "Default")
      (node (ref "R14") (pin "1") (pinfunction "1_1") (pintype "input"))
      (node (ref "U1") (pin "15") (pinfunction "15_15") (pintype "unspecified"))
      (node (ref "U15") (pin "1") (pinfunction "1_1") (pintype "unspecified"))
      (node (ref "U4") (pin "13") (pinfunction "SCX_13") (pintype "unspecified"))
    )
    (net (code "12") (name "I2C_SDA") (class "Default")
      (node (ref "R13") (pin "1") (pinfunction "1_1") (pintype "input"))
      (node (ref "U1") (pin "17") (pinfunction "17_17") (pintype "unspecified"))
      (node (ref "U15") (pin "2") (pinfunction "2_2") (pintype "unspecified"))
      (node (ref "U4") (pin "14") (pinfunction "SDX_14") (pintype "unspecified"))
    )
    (net (code "13") (name "KEY_DOWN") (class "Default")
      (node (ref "R7") (pin "1") (pinfunction "1_1") (pintype "input"))
      (node (ref "SW1") (pin "4") (pinfunction "4_4") (pintype "unspecified"))
      (node (ref "U1") (pin "11") (pinfunction "11_11") (pintype "unspecified"))
    )
    (net (code "14") (name "KEY_LEFT") (class "Default")
      (node (ref "R6") (pin "2") (pinfunction "2_2") (pintype "input"))
      (node (ref "SW1") (pin "3") (pinfunction "3_3") (pintype "unspecified"))
      (node (ref "U1") (pin "9") (pinfunction "9_9") (pintype "unspecified"))
    )
    (net (code "15") (name "KEY_MID") (class "Default")
      (node (ref "R5") (pin "1") (pinfunction "1_1") (pintype "input"))
      (node (ref "SW1") (pin "5") (pinfunction "5_5") (pintype "unspecified"))
      (node (ref "U1") (pin "14") (pinfunction "14_14") (pintype "unspecified"))
    )
    (net (code "16") (name "KEY_RIGHT") (class "Default")
      (node (ref "R3") (pin "1") (pinfunction "1_1") (pintype "input"))
      (node (ref "SW1") (pin "6") (pinfunction "6_6") (pintype "unspecified"))
      (node (ref "U1") (pin "7") (pinfunction "7_7") (pintype "unspecified"))
    )
    (net (code "17") (name "KEY_UP") (class "Default")
      (node (ref "R1") (pin "2") (pinfunction "2_2") (pintype "input"))
      (node (ref "SW1") (pin "1") (pinfunction "1_1") (pintype "unspecified"))
      (node (ref "U1") (pin "25") (pinfunction "25_25") (pintype "unspecified"))
    )
    (net (code "18") (name "MOTOR_DIR_L") (class "Default")
      (node (ref "R12") (pin "2") (pinfunction "2_2") (pintype "input"))
      (node (ref "U1") (pin "8") (pinfunction "8_8") (pintype "unspecified"))
    )
    (net (code "19") (name "MOTOR_DIR_R") (class "Default")
      (node (ref "R11") (pin "1") (pinfunction "1_1") (pintype "input"))
      (node (ref "U1") (pin "10") (pinfunction "10_10") (pintype "unspecified"))
    )
    (net (code "20") (name "MOTOR_PWM_L") (class "Default")
      (node (ref "R18") (pin "2") (pinfunction "2_2") (pintype "input"))
      (node (ref "U1") (pin "26") (pinfunction "26_26") (pintype "unspecified"))
    )
    (net (code "21") (name "MOTOR_PWM_R") (class "Default")
      (node (ref "R17") (pin "1") (pinfunction "1_1") (pintype "input"))
      (node (ref "U1") (pin "28") (pinfunction "28_28") (pintype "unspecified"))
    )
    (net (code "22") (name "Net-(BUZZER2--)") (class "Default")
      (node (ref "BUZZER2") (pin "2") (pinfunction "-_2") (pintype "unspecified"))
      (node (ref "D3") (pin "2") (pinfunction "A_2") (pintype "unspecified"))
      (node (ref "Q3") (pin "3") (pinfunction "3_3") (pintype "input"))
    )
    (net (code "23") (name "Net-(C23-Pad2)") (class "Default")
      (node (ref "C23") (pin "2") (pinfunction "2_2") (pintype "unspecified"))
      (node (ref "R35") (pin "1") (pinfunction "1_1") (pintype "input"))
    )
    (net (code "24") (name "Net-(CN1-+)") (class "Default")
      (node (ref "CN1") (pin "2") (pinfunction "+_2") (pintype "unspecified"))
      (node (ref "D4") (pin "1") (pinfunction "K_1") (pintype "unspecified"))
      (node (ref "Q6") (pin "1") (pinfunction "S_1") (pintype "unspecified"))
      (node (ref "Q6") (pin "2") (pinfunction "S_2") (pintype "unspecified"))
      (node (ref "Q6") (pin "3") (pinfunction "S_3") (pintype "unspecified"))
      (node (ref "U8") (pin "3") (pinfunction "3_3") (pintype "unspecified"))
    )
    (net (code "25") (name "Net-(D4-A)") (class "Default")
      (node (ref "D4") (pin "2") (pinfunction "A_2") (pintype "unspecified"))
      (node (ref "R27") (pin "2") (pinfunction "2_2") (pintype "input"))
      (node (ref "U8") (pin "1") (pinfunction "1_1") (pintype "unspecified"))
    )
    (net (code "26") (name "Net-(D5-A)") (class "Default")
      (node (ref "C14") (pin "2") (pinfunction "2_2") (pintype "unspecified"))
      (node (ref "C29") (pin "1") (pinfunction "1_1") (pintype "input"))
      (node (ref "D5") (pin "1") (pinfunction "A_1") (pintype "unspecified"))
      (node (ref "L1") (pin "2") (pinfunction "2_2") (pintype "unspecified"))
    )
    (net (code "27") (name "Net-(D6-K)") (class "Default")
      (node (ref "C21") (pin "2") (pinfunction "2_2") (pintype "unspecified"))
      (node (ref "C22") (pin "2") (pinfunction "2_2") (pintype "unspecified"))
      (node (ref "C28") (pin "1") (pinfunction "1_1") (pintype "input"))
      (node (ref "D6") (pin "2") (pinfunction "K_2") (pintype "unspecified"))
      (node (ref "U6") (pin "2") (pinfunction "VIN_2") (pintype "unspecified"))
      (node (ref "U6") (pin "3") (pinfunction "EN_3") (pintype "unspecified"))
    )
    (net (code "28") (name "Net-(H11-Pad1)") (class "Default")
      (node (ref "H11") (pin "1") (pinfunction "1_1") (pintype "unspecified"))
      (node (ref "R11") (pin "2") (pinfunction "2_2") (pintype "input"))
    )
    (net (code "29") (name "Net-(H11-Pad2)") (class "Default")
      (node (ref "H11") (pin "2") (pinfunction "2_2") (pintype "unspecified"))
      (node (ref "R12") (pin "1") (pinfunction "1_1") (pintype "input"))
    )
    (net (code "30") (name "Net-(H11-Pad5)") (class "Default")
      (node (ref "H11") (pin "5") (pinfunction "5_5") (pintype "unspecified"))
      (node (ref "R17") (pin "2") (pinfunction "2_2") (pintype "input"))
    )
    (net (code "31") (name "Net-(H11-Pad6)") (class "Default")
      (node (ref "H11") (pin "6") (pinfunction "6_6") (pintype "unspecified"))
      (node (ref "R18") (pin "1") (pinfunction "1_1") (pintype "input"))
    )
    (net (code "32") (name "Net-(H12-Pad5)") (class "Default")
      (node (ref "H12") (pin "5") (pinfunction "5_5") (pintype "unspecified"))
      (node (ref "R26") (pin "1") (pinfunction "1_1") (pintype "input"))
    )
    (net (code "33") (name "Net-(H12-Pad6)") (class "Default")
      (node (ref "H12") (pin "6") (pinfunction "6_6") (pintype "unspecified"))
      (node (ref "R25") (pin "1") (pinfunction "1_1") (pintype "input"))
    )
    (net (code "34") (name "Net-(LED3-A)") (class "Default")
      (node (ref "LED3") (pin "2") (pinfunction "A_2") (pintype "input"))
      (node (ref "R29") (pin "1") (pinfunction "1_1") (pintype "input"))
    )
    (net (code "35") (name "Net-(LED4-A)") (class "Default")
      (node (ref "LED4") (pin "2") (pinfunction "A_2") (pintype "input"))
      (node (ref "R32") (pin "2") (pinfunction "2_2") (pintype "input"))
    )
    (net (code "36") (name "Net-(Q3-Pad1)") (class "Default")
      (node (ref "Q3") (pin "1") (pinfunction "1_1") (pintype "input"))
      (node (ref "R21") (pin "2") (pinfunction "2_2") (pintype "input"))
      (node (ref "R22") (pin "1") (pinfunction "1_1") (pintype "input"))
    )
    (net (code "37") (name "Net-(Q6-G)") (class "Default")
      (node (ref "Q6") (pin "4") (pinfunction "G_4") (pintype "unspecified"))
      (node (ref "R36") (pin "2") (pinfunction "2_2") (pintype "input"))
    )
    (net (code "38") (name "Net-(Q7-D)") (class "Default")
      (node (ref "Q7") (pin "3") (pinfunction "D_3") (pintype "unspecified"))
      (node (ref "Q8") (pin "3") (pinfunction "D_3") (pintype "unspecified"))
    )
    (net (code "39") (name "Net-(R30-Pad1)") (class "Default")
      (node (ref "R30") (pin "1") (pinfunction "1_1") (pintype "input"))
      (node (ref "R31") (pin "2") (pinfunction "2_2") (pintype "input"))
    )
    (net (code "40") (name "Net-(R36-Pad1)") (class "Default")
      (node (ref "R36") (pin "1") (pinfunction "1_1") (pintype "input"))
      (node (ref "U8") (pin "2") (pinfunction "2_2") (pintype "unspecified"))
    )
    (net (code "41") (name "Net-(U6-BOOT)") (class "Default")
      (node (ref "C13") (pin "2") (pinfunction "2_2") (pintype "unspecified"))
      (node (ref "U6") (pin "1") (pinfunction "BOOT_1") (pintype "unspecified"))
    )
    (net (code "42") (name "Net-(U6-COMP)") (class "Default")
      (node (ref "R35") (pin "2") (pinfunction "2_2") (pintype "input"))
      (node (ref "U6") (pin "6") (pinfunction "COMP_6") (pintype "unspecified"))
    )
    (net (code "43") (name "Net-(U6-FB)") (class "Default")
      (node (ref "R31") (pin "1") (pinfunction "1_1") (pintype "input"))
      (node (ref "R33") (pin "2") (pinfunction "2_2") (pintype "input"))
      (node (ref "U6") (pin "5") (pinfunction "FB_5") (pintype "unspecified"))
    )
    (net (code "44") (name "Net-(U6-RT{slash}CLK)") (class "Default")
      (node (ref "R34") (pin "2") (pinfunction "2_2") (pintype "input"))
      (node (ref "U6") (pin "4") (pinfunction "RT/CLK_4") (pintype "unspecified"))
    )
    (net (code "45") (name "Net-(U6-SW)") (class "Default")
      (node (ref "C13") (pin "1") (pinfunction "1_1") (pintype "unspecified"))
      (node (ref "L1") (pin "1") (pinfunction "1_1") (pintype "unspecified"))
      (node (ref "U6") (pin "8") (pinfunction "SW_8") (pintype "unspecified"))
    )
    (net (code "46") (name "Net-(U9-V3)") (class "Default")
      (node (ref "C26") (pin "1") (pinfunction "1_1") (pintype "unspecified"))
      (node (ref "U9") (pin "6") (pinfunction "V3_6") (pintype "unspecified"))
    )
    (net (code "47") (name "Net-(USB1-CC1)") (class "Default")
      (node (ref "R8") (pin "1") (pinfunction "1_1") (pintype "input"))
      (node (ref "USB1") (pin "4") (pinfunction "CC1_4") (pintype "unspecified"))
    )
    (net (code "48") (name "Net-(USB1-CC2)") (class "Default")
      (node (ref "R4") (pin "1") (pinfunction "1_1") (pintype "input"))
      (node (ref "USB1") (pin "10") (pinfunction "CC2_10") (pintype "unspecified"))
    )
    (net (code "49") (name "RX") (class "Default")
      (node (ref "U1") (pin "5") (pinfunction "5_5") (pintype "unspecified"))
      (node (ref "U13") (pin "3") (pinfunction "3_3") (pintype "unspecified"))
      (node (ref "U9") (pin "4") (pinfunction "TXD_4") (pintype "unspecified"))
    )
    (net (code "50") (name "TFFT180_SDA") (class "Default")
      (node (ref "FPC1") (pin "8") (pinfunction "8_8") (pintype "unspecified"))
      (node (ref "U1") (pin "27") (pinfunction "27_27") (pintype "unspecified"))
    )
    (net (code "51") (name "TFT180_CS") (class "Default")
      (node (ref "FPC1") (pin "12") (pinfunction "12_12") (pintype "unspecified"))
      (node (ref "U1") (pin "23") (pinfunction "23_23") (pintype "unspecified"))
    )
    (net (code "52") (name "TFT180_DC") (class "Default")
      (node (ref "FPC1") (pin "7") (pinfunction "7_7") (pintype "unspecified"))
      (node (ref "U1") (pin "12") (pinfunction "12_12") (pintype "unspecified"))
    )
    (net (code "53") (name "TFT180_RES") (class "Default")
      (node (ref "FPC1") (pin "6") (pinfunction "6_6") (pintype "unspecified"))
      (node (ref "U1") (pin "13") (pinfunction "13_13") (pintype "unspecified"))
    )
    (net (code "54") (name "TFT180_SCL") (class "Default")
      (node (ref "FPC1") (pin "9") (pinfunction "9_9") (pintype "unspecified"))
      (node (ref "U1") (pin "21") (pinfunction "21_21") (pintype "unspecified"))
    )
    (net (code "55") (name "TX") (class "Default")
      (node (ref "U1") (pin "3") (pinfunction "3_3") (pintype "unspecified"))
      (node (ref "U13") (pin "1") (pinfunction "1_1") (pintype "unspecified"))
      (node (ref "U9") (pin "5") (pinfunction "RXD_5") (pintype "unspecified"))
    )
    (net (code "56") (name "UD+") (class "Default")
      (node (ref "U9") (pin "7") (pinfunction "UD+_7") (pintype "unspecified"))
      (node (ref "USB1") (pin "6") (pinfunction "DP1_6") (pintype "unspecified"))
      (node (ref "USB1") (pin "8") (pinfunction "DP2_8") (pintype "unspecified"))
    )
    (net (code "57") (name "UD-") (class "Default")
      (node (ref "U9") (pin "8") (pinfunction "UD-_8") (pintype "unspecified"))
      (node (ref "USB1") (pin "5") (pinfunction "DN2_5") (pintype "unspecified"))
      (node (ref "USB1") (pin "7") (pinfunction "DN1_7") (pintype "unspecified"))
    )
    (net (code "58") (name "VCCBAT") (class "Default")
      (node (ref "D6") (pin "1") (pinfunction "A_1") (pintype "unspecified"))
      (node (ref "Q6") (pin "5") (pinfunction "D_5") (pintype "unspecified"))
    )
    (net (code "59") (name "VCCBAT_5V") (class "Default")
      (node (ref "D5") (pin "2") (pinfunction "K_2") (pintype "unspecified"))
      (node (ref "Q8") (pin "2") (pinfunction "S_2") (pintype "unspecified"))
      (node (ref "R30") (pin "2") (pinfunction "2_2") (pintype "input"))
    )
    (net (code "60") (name "VCCUSB") (class "Default")
      (node (ref "D2") (pin "2") (pinfunction "A_2") (pintype "unspecified"))
      (node (ref "Q7") (pin "1") (pinfunction "G_1") (pintype "unspecified"))
      (node (ref "Q8") (pin "1") (pinfunction "G_1") (pintype "unspecified"))
      (node (ref "R37") (pin "2") (pinfunction "2_2") (pintype "input"))
      (node (ref "USB1") (pin "11") (pinfunction "VBUS_11") (pintype "unspecified"))
      (node (ref "USB1") (pin "2") (pinfunction "VBUS_2") (pintype "unspecified"))
    )
    (net (code "61") (name "unconnected-(FPC1-Pad1)") (class "Default")
      (node (ref "FPC1") (pin "1") (pinfunction "1_1") (pintype "unspecified+no_connect"))
    )
    (net (code "62") (name "unconnected-(FPC1-Pad14)") (class "Default")
      (node (ref "FPC1") (pin "14") (pinfunction "14_14") (pintype "unspecified+no_connect"))
    )
    (net (code "63") (name "unconnected-(H12-Pad3)") (class "Default")
      (node (ref "H12") (pin "3") (pinfunction "3_3") (pintype "unspecified+no_connect"))
    )
    (net (code "64") (name "unconnected-(H12-Pad4)") (class "Default")
      (node (ref "H12") (pin "4") (pinfunction "4_4") (pintype "unspecified+no_connect"))
    )
    (net (code "65") (name "unconnected-(H13-Pad1)") (class "Default")
      (node (ref "H13") (pin "1") (pinfunction "1_1") (pintype "unspecified+no_connect"))
    )
    (net (code "66") (name "unconnected-(H13-Pad2)") (class "Default")
      (node (ref "H13") (pin "2") (pinfunction "2_2") (pintype "unspecified+no_connect"))
    )
    (net (code "67") (name "unconnected-(H14-Pad1)") (class "Default")
      (node (ref "H14") (pin "1") (pinfunction "1_1") (pintype "unspecified+no_connect"))
    )
    (net (code "68") (name "unconnected-(H14-Pad2)") (class "Default")
      (node (ref "H14") (pin "2") (pinfunction "2_2") (pintype "unspecified+no_connect"))
    )
    (net (code "69") (name "unconnected-(U1-Pad1)") (class "Default")
      (node (ref "U1") (pin "1") (pinfunction "1_1") (pintype "unspecified+no_connect"))
    )
    (net (code "70") (name "unconnected-(U2-Pad1)") (class "Default")
      (node (ref "U2") (pin "1") (pinfunction "1_1") (pintype "unspecified+no_connect"))
    )
    (net (code "71") (name "unconnected-(U2-Pad2)") (class "Default")
      (node (ref "U2") (pin "2") (pinfunction "2_2") (pintype "unspecified+no_connect"))
    )
    (net (code "72") (name "unconnected-(U2-Pad3)") (class "Default")
      (node (ref "U2") (pin "3") (pinfunction "3_3") (pintype "unspecified+no_connect"))
    )
    (net (code "73") (name "unconnected-(U2-Pad4)") (class "Default")
      (node (ref "U2") (pin "4") (pinfunction "4_4") (pintype "unspecified+no_connect"))
    )
    (net (code "74") (name "unconnected-(U2-Pad5)") (class "Default")
      (node (ref "U2") (pin "5") (pinfunction "5_5") (pintype "unspecified+no_connect"))
    )
    (net (code "75") (name "unconnected-(U2-Pad6)") (class "Default")
      (node (ref "U2") (pin "6") (pinfunction "6_6") (pintype "unspecified+no_connect"))
    )
    (net (code "76") (name "unconnected-(U2-Pad7)") (class "Default")
      (node (ref "U2") (pin "7") (pinfunction "7_7") (pintype "unspecified+no_connect"))
    )
    (net (code "77") (name "unconnected-(U2-Pad8)") (class "Default")
      (node (ref "U2") (pin "8") (pinfunction "8_8") (pintype "unspecified+no_connect"))
    )
    (net (code "78") (name "unconnected-(U2-Pad9)") (class "Default")
      (node (ref "U2") (pin "9") (pinfunction "9_9") (pintype "unspecified+no_connect"))
    )
    (net (code "79") (name "unconnected-(U2-Pad10)") (class "Default")
      (node (ref "U2") (pin "10") (pinfunction "10_10") (pintype "unspecified+no_connect"))
    )
    (net (code "80") (name "unconnected-(U4-ASCX-Pad3)") (class "Default")
      (node (ref "U4") (pin "3") (pinfunction "ASCX_3") (pintype "unspecified+no_connect"))
    )
    (net (code "81") (name "unconnected-(U4-ASDX-Pad2)") (class "Default")
      (node (ref "U4") (pin "2") (pinfunction "ASDX_2") (pintype "unspecified+no_connect"))
    )
    (net (code "82") (name "unconnected-(U4-CSB-Pad12)") (class "Default")
      (node (ref "U4") (pin "12") (pinfunction "CSB_12") (pintype "unspecified+no_connect"))
    )
    (net (code "83") (name "unconnected-(U4-INT1-Pad4)") (class "Default")
      (node (ref "U4") (pin "4") (pinfunction "INT1_4") (pintype "unspecified+no_connect"))
    )
    (net (code "84") (name "unconnected-(U4-INT2-Pad9)") (class "Default")
      (node (ref "U4") (pin "9") (pinfunction "INT2_9") (pintype "unspecified+no_connect"))
    )
    (net (code "85") (name "unconnected-(U4-OCSB-Pad10)") (class "Default")
      (node (ref "U4") (pin "10") (pinfunction "OCSB_10") (pintype "unspecified+no_connect"))
    )
    (net (code "86") (name "unconnected-(U4-OSDO-Pad11)") (class "Default")
      (node (ref "U4") (pin "11") (pinfunction "OSDO_11") (pintype "unspecified+no_connect"))
    )
    (net (code "87") (name "unconnected-(U7-NC-Pad4)") (class "Default")
      (node (ref "U7") (pin "4") (pinfunction "NC_4") (pintype "unspecified+no_connect"))
    )
    (net (code "88") (name "unconnected-(U9-ACT#-Pad10)") (class "Default")
      (node (ref "U9") (pin "10") (pinfunction "ACT#_10") (pintype "unspecified+no_connect"))
    )
    (net (code "89") (name "unconnected-(U9-CTS-Pad15)") (class "Default")
      (node (ref "U9") (pin "15") (pinfunction "CTS_15") (pintype "unspecified+no_connect"))
    )
    (net (code "90") (name "unconnected-(U9-DCD-Pad11)") (class "Default")
      (node (ref "U9") (pin "11") (pinfunction "DCD_11") (pintype "unspecified+no_connect"))
    )
    (net (code "91") (name "unconnected-(U9-DSR-Pad14)") (class "Default")
      (node (ref "U9") (pin "14") (pinfunction "DSR_14") (pintype "unspecified+no_connect"))
    )
    (net (code "92") (name "unconnected-(U9-DTRTNOW-Pad12)") (class "Default")
      (node (ref "U9") (pin "12") (pinfunction "DTRTNOW_12") (pintype "unspecified+no_connect"))
    )
    (net (code "93") (name "unconnected-(U9-RI-Pad16)") (class "Default")
      (node (ref "U9") (pin "16") (pinfunction "RI_16") (pintype "unspecified+no_connect"))
    )
    (net (code "94") (name "unconnected-(U9-RTS-Pad13)") (class "Default")
      (node (ref "U9") (pin "13") (pinfunction "RTS_13") (pintype "unspecified+no_connect"))
    )
    (net (code "95") (name "unconnected-(U13-Pad2)") (class "Default")
      (node (ref "U13") (pin "2") (pinfunction "2_2") (pintype "unspecified+no_connect"))
    )
    (net (code "96") (name "unconnected-(U13-Pad4)") (class "Default")
      (node (ref "U13") (pin "4") (pinfunction "4_4") (pintype "unspecified+no_connect"))
    )
    (net (code "97") (name "unconnected-(U13-Pad6)") (class "Default")
      (node (ref "U13") (pin "6") (pinfunction "6_6") (pintype "unspecified+no_connect"))
    )
    (net (code "98") (name "unconnected-(U13-Pad8)") (class "Default")
      (node (ref "U13") (pin "8") (pinfunction "8_8") (pintype "unspecified+no_connect"))
    )
    (net (code "99") (name "unconnected-(USB1-SBU1-Pad9)") (class "Default")
      (node (ref "USB1") (pin "9") (pinfunction "SBU1_9") (pintype "unspecified+no_connect"))
    )
    (net (code "100") (name "unconnected-(USB1-SBU2-Pad3)") (class "Default")
      (node (ref "USB1") (pin "3") (pinfunction "SBU2_3") (pintype "unspecified+no_connect"))
    )
  )
)
